# 324_Electrode_Wafer_Schematic.net
KiCad netlist of a schematic drawn in Altium Designer
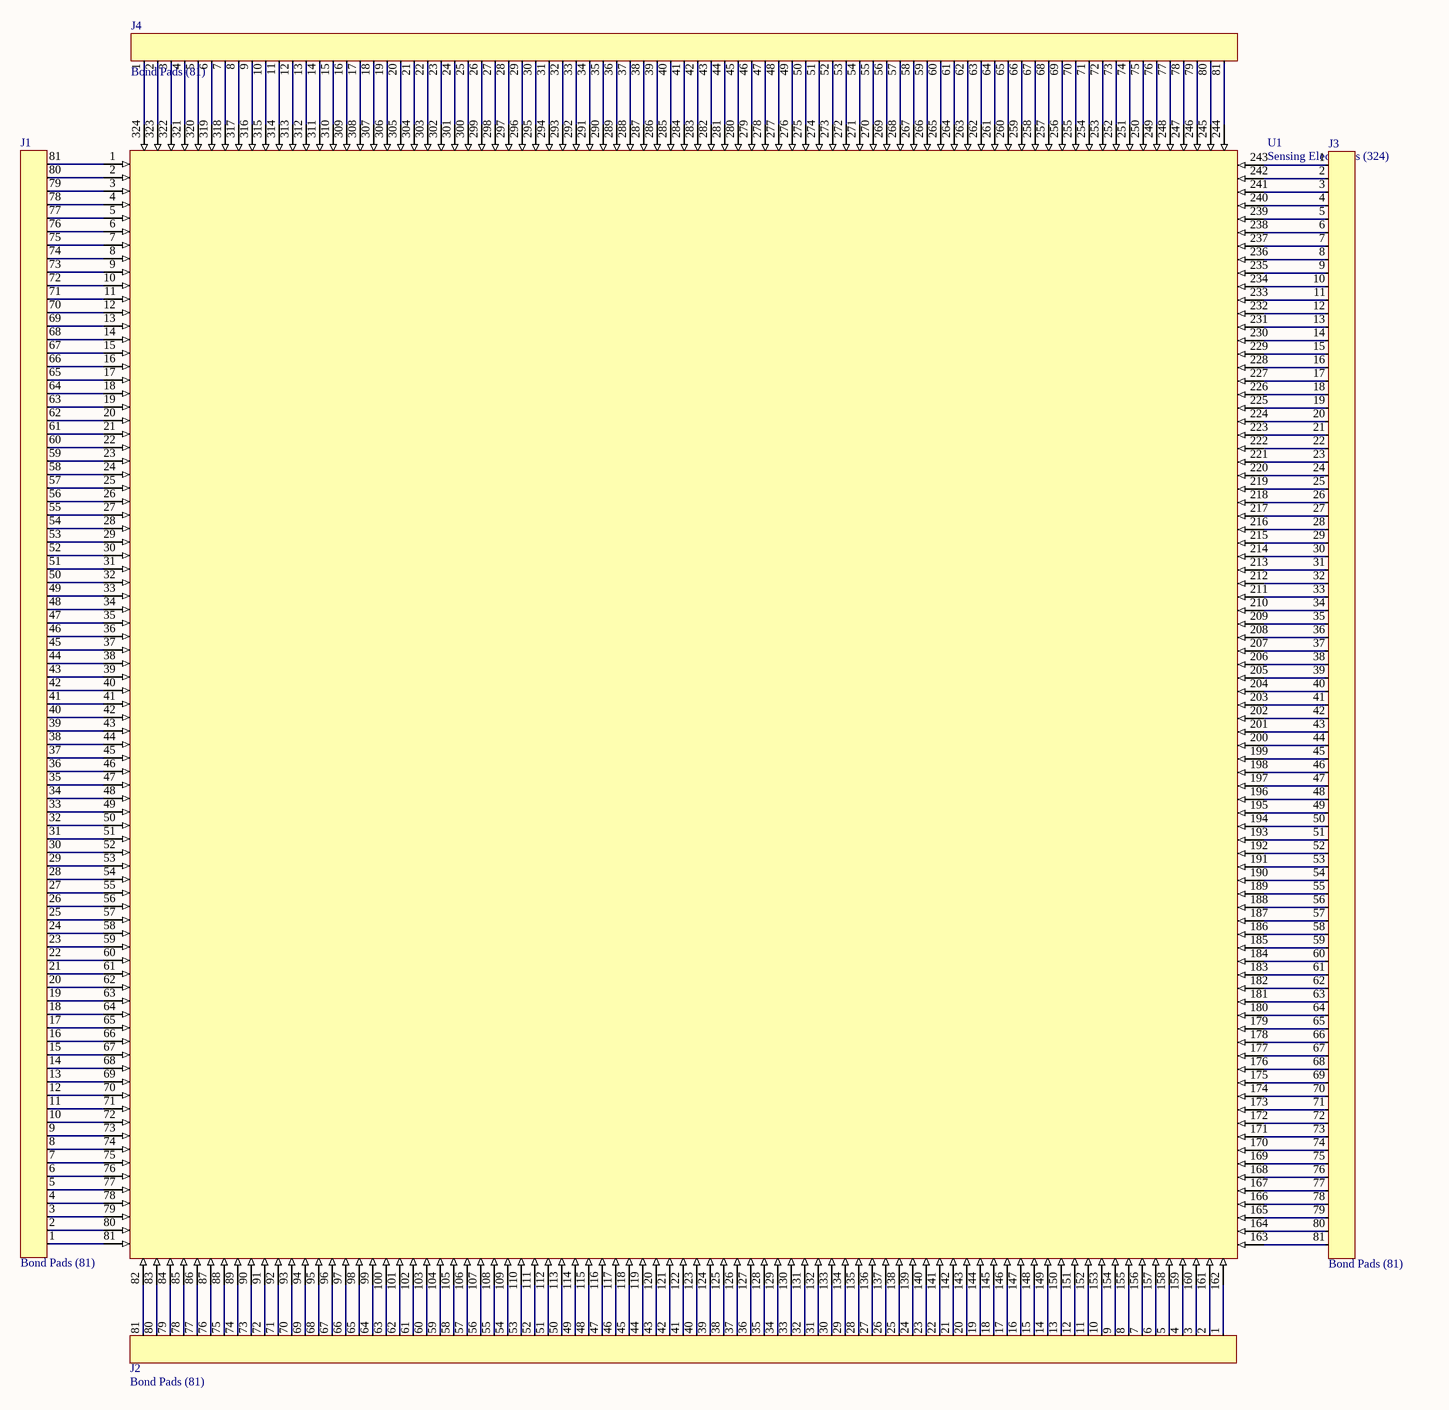
[diagram p0: 324 Electrode Wafer Schematic.SchDoc]

(export (version "E")
  (design (tool "Eeschema 10.0.6"))
  (components
    (comp (ref "J1")
      (value "Bond Pads (81)")
      (footprint "Bond Pads (81)")
      (description "81 pads for all four sides of the chip")
      (libsource (lib "") (part "Bond Pads (81)_1"))
    )
    (comp (ref "J2")
      (value "Bond Pads (81)")
      (footprint "Bond Pads (81)")
      (description "81 pads for all four sides of the chip")
      (libsource (lib "") (part "Bond Pads (81)_3"))
    )
    (comp (ref "J3")
      (value "Bond Pads (81)")
      (footprint "Bond Pads (81)")
      (description "81 pads for all four sides of the chip")
      (libsource (lib "Celestial Library Database") (part "Bond Pads (81)"))
    )
    (comp (ref "J4")
      (value "Bond Pads (81)")
      (footprint "Bond Pads (81)")
      (description "81 pads for all four sides of the chip")
      (libsource (lib "") (part "Bond Pads (81)_2"))
    )
    (comp (ref "U1")
      (value "Sensing Electrodes (324)")
      (footprint "Sensing Area (324)")
      (description "324 Electrodes covering a 2mm by 2mm sensing 10x")
      (fields (field (name "PART NUMBER") "Silicon Die Holder 324 Electrodes"))
      (libsource (lib "Celestial Library Database") (part "Sensing Electrodes (324)"))
    )
  )
  (nets
    (net (code "1") (name "Net-(J1-Pad1)") (class "Default")
      (node (ref "J1") (pin "1") (pintype "input"))
      (node (ref "U1") (pin "81") (pintype "input"))
    )
    (net (code "2") (name "Net-(J1-Pad2)") (class "Default")
      (node (ref "J1") (pin "2") (pintype "input"))
      (node (ref "U1") (pin "80") (pintype "input"))
    )
    (net (code "3") (name "Net-(J1-Pad3)") (class "Default")
      (node (ref "J1") (pin "3") (pintype "input"))
      (node (ref "U1") (pin "79") (pintype "input"))
    )
    (net (code "4") (name "Net-(J1-Pad4)") (class "Default")
      (node (ref "J1") (pin "4") (pintype "input"))
      (node (ref "U1") (pin "78") (pintype "input"))
    )
    (net (code "5") (name "Net-(J1-Pad5)") (class "Default")
      (node (ref "J1") (pin "5") (pintype "input"))
      (node (ref "U1") (pin "77") (pintype "input"))
    )
    (net (code "6") (name "Net-(J1-Pad6)") (class "Default")
      (node (ref "J1") (pin "6") (pintype "input"))
      (node (ref "U1") (pin "76") (pintype "input"))
    )
    (net (code "7") (name "Net-(J1-Pad7)") (class "Default")
      (node (ref "J1") (pin "7") (pintype "input"))
      (node (ref "U1") (pin "75") (pintype "input"))
    )
    (net (code "8") (name "Net-(J1-Pad8)") (class "Default")
      (node (ref "J1") (pin "8") (pintype "input"))
      (node (ref "U1") (pin "74") (pintype "input"))
    )
    (net (code "9") (name "Net-(J1-Pad9)") (class "Default")
      (node (ref "J1") (pin "9") (pintype "input"))
      (node (ref "U1") (pin "73") (pintype "input"))
    )
    (net (code "10") (name "Net-(J1-Pad10)") (class "Default")
      (node (ref "J1") (pin "10") (pintype "input"))
      (node (ref "U1") (pin "72") (pintype "input"))
    )
    (net (code "11") (name "Net-(J1-Pad11)") (class "Default")
      (node (ref "J1") (pin "11") (pintype "input"))
      (node (ref "U1") (pin "71") (pintype "input"))
    )
    (net (code "12") (name "Net-(J1-Pad12)") (class "Default")
      (node (ref "J1") (pin "12") (pintype "input"))
      (node (ref "U1") (pin "70") (pintype "input"))
    )
    (net (code "13") (name "Net-(J1-Pad13)") (class "Default")
      (node (ref "J1") (pin "13") (pintype "input"))
      (node (ref "U1") (pin "69") (pintype "input"))
    )
    (net (code "14") (name "Net-(J1-Pad14)") (class "Default")
      (node (ref "J1") (pin "14") (pintype "input"))
      (node (ref "U1") (pin "68") (pintype "input"))
    )
    (net (code "15") (name "Net-(J1-Pad15)") (class "Default")
      (node (ref "J1") (pin "15") (pintype "input"))
      (node (ref "U1") (pin "67") (pintype "input"))
    )
    (net (code "16") (name "Net-(J1-Pad16)") (class "Default")
      (node (ref "J1") (pin "16") (pintype "input"))
      (node (ref "U1") (pin "66") (pintype "input"))
    )
    (net (code "17") (name "Net-(J1-Pad17)") (class "Default")
      (node (ref "J1") (pin "17") (pintype "input"))
      (node (ref "U1") (pin "65") (pintype "input"))
    )
    (net (code "18") (name "Net-(J1-Pad18)") (class "Default")
      (node (ref "J1") (pin "18") (pintype "input"))
      (node (ref "U1") (pin "64") (pintype "input"))
    )
    (net (code "19") (name "Net-(J1-Pad19)") (class "Default")
      (node (ref "J1") (pin "19") (pintype "input"))
      (node (ref "U1") (pin "63") (pintype "input"))
    )
    (net (code "20") (name "Net-(J1-Pad20)") (class "Default")
      (node (ref "J1") (pin "20") (pintype "input"))
      (node (ref "U1") (pin "62") (pintype "input"))
    )
    (net (code "21") (name "Net-(J1-Pad21)") (class "Default")
      (node (ref "J1") (pin "21") (pintype "input"))
      (node (ref "U1") (pin "61") (pintype "input"))
    )
    (net (code "22") (name "Net-(J1-Pad22)") (class "Default")
      (node (ref "J1") (pin "22") (pintype "input"))
      (node (ref "U1") (pin "60") (pintype "input"))
    )
    (net (code "23") (name "Net-(J1-Pad23)") (class "Default")
      (node (ref "J1") (pin "23") (pintype "input"))
      (node (ref "U1") (pin "59") (pintype "input"))
    )
    (net (code "24") (name "Net-(J1-Pad24)") (class "Default")
      (node (ref "J1") (pin "24") (pintype "input"))
      (node (ref "U1") (pin "58") (pintype "input"))
    )
    (net (code "25") (name "Net-(J1-Pad25)") (class "Default")
      (node (ref "J1") (pin "25") (pintype "input"))
      (node (ref "U1") (pin "57") (pintype "input"))
    )
    (net (code "26") (name "Net-(J1-Pad26)") (class "Default")
      (node (ref "J1") (pin "26") (pintype "input"))
      (node (ref "U1") (pin "56") (pintype "input"))
    )
    (net (code "27") (name "Net-(J1-Pad27)") (class "Default")
      (node (ref "J1") (pin "27") (pintype "input"))
      (node (ref "U1") (pin "55") (pintype "input"))
    )
    (net (code "28") (name "Net-(J1-Pad28)") (class "Default")
      (node (ref "J1") (pin "28") (pintype "input"))
      (node (ref "U1") (pin "54") (pintype "input"))
    )
    (net (code "29") (name "Net-(J1-Pad29)") (class "Default")
      (node (ref "J1") (pin "29") (pintype "input"))
      (node (ref "U1") (pin "53") (pintype "input"))
    )
    (net (code "30") (name "Net-(J1-Pad30)") (class "Default")
      (node (ref "J1") (pin "30") (pintype "input"))
      (node (ref "U1") (pin "52") (pintype "input"))
    )
    (net (code "31") (name "Net-(J1-Pad31)") (class "Default")
      (node (ref "J1") (pin "31") (pintype "input"))
      (node (ref "U1") (pin "51") (pintype "input"))
    )
    (net (code "32") (name "Net-(J1-Pad32)") (class "Default")
      (node (ref "J1") (pin "32") (pintype "input"))
      (node (ref "U1") (pin "50") (pintype "input"))
    )
    (net (code "33") (name "Net-(J1-Pad33)") (class "Default")
      (node (ref "J1") (pin "33") (pintype "input"))
      (node (ref "U1") (pin "49") (pintype "input"))
    )
    (net (code "34") (name "Net-(J1-Pad34)") (class "Default")
      (node (ref "J1") (pin "34") (pintype "input"))
      (node (ref "U1") (pin "48") (pintype "input"))
    )
    (net (code "35") (name "Net-(J1-Pad35)") (class "Default")
      (node (ref "J1") (pin "35") (pintype "input"))
      (node (ref "U1") (pin "47") (pintype "input"))
    )
    (net (code "36") (name "Net-(J1-Pad36)") (class "Default")
      (node (ref "J1") (pin "36") (pintype "input"))
      (node (ref "U1") (pin "46") (pintype "input"))
    )
    (net (code "37") (name "Net-(J1-Pad37)") (class "Default")
      (node (ref "J1") (pin "37") (pintype "input"))
      (node (ref "U1") (pin "45") (pintype "input"))
    )
    (net (code "38") (name "Net-(J1-Pad38)") (class "Default")
      (node (ref "J1") (pin "38") (pintype "input"))
      (node (ref "U1") (pin "44") (pintype "input"))
    )
    (net (code "39") (name "Net-(J1-Pad39)") (class "Default")
      (node (ref "J1") (pin "39") (pintype "input"))
      (node (ref "U1") (pin "43") (pintype "input"))
    )
    (net (code "40") (name "Net-(J1-Pad40)") (class "Default")
      (node (ref "J1") (pin "40") (pintype "input"))
      (node (ref "U1") (pin "42") (pintype "input"))
    )
    (net (code "41") (name "Net-(J1-Pad41)") (class "Default")
      (node (ref "J1") (pin "41") (pintype "input"))
      (node (ref "U1") (pin "41") (pintype "input"))
    )
    (net (code "42") (name "Net-(J1-Pad42)") (class "Default")
      (node (ref "J1") (pin "42") (pintype "input"))
      (node (ref "U1") (pin "40") (pintype "input"))
    )
    (net (code "43") (name "Net-(J1-Pad43)") (class "Default")
      (node (ref "J1") (pin "43") (pintype "input"))
      (node (ref "U1") (pin "39") (pintype "input"))
    )
    (net (code "44") (name "Net-(J1-Pad44)") (class "Default")
      (node (ref "J1") (pin "44") (pintype "input"))
      (node (ref "U1") (pin "38") (pintype "input"))
    )
    (net (code "45") (name "Net-(J1-Pad45)") (class "Default")
      (node (ref "J1") (pin "45") (pintype "input"))
      (node (ref "U1") (pin "37") (pintype "input"))
    )
    (net (code "46") (name "Net-(J1-Pad46)") (class "Default")
      (node (ref "J1") (pin "46") (pintype "input"))
      (node (ref "U1") (pin "36") (pintype "input"))
    )
    (net (code "47") (name "Net-(J1-Pad47)") (class "Default")
      (node (ref "J1") (pin "47") (pintype "input"))
      (node (ref "U1") (pin "35") (pintype "input"))
    )
    (net (code "48") (name "Net-(J1-Pad48)") (class "Default")
      (node (ref "J1") (pin "48") (pintype "input"))
      (node (ref "U1") (pin "34") (pintype "input"))
    )
    (net (code "49") (name "Net-(J1-Pad49)") (class "Default")
      (node (ref "J1") (pin "49") (pintype "input"))
      (node (ref "U1") (pin "33") (pintype "input"))
    )
    (net (code "50") (name "Net-(J1-Pad50)") (class "Default")
      (node (ref "J1") (pin "50") (pintype "input"))
      (node (ref "U1") (pin "32") (pintype "input"))
    )
    (net (code "51") (name "Net-(J1-Pad51)") (class "Default")
      (node (ref "J1") (pin "51") (pintype "input"))
      (node (ref "U1") (pin "31") (pintype "input"))
    )
    (net (code "52") (name "Net-(J1-Pad52)") (class "Default")
      (node (ref "J1") (pin "52") (pintype "input"))
      (node (ref "U1") (pin "30") (pintype "input"))
    )
    (net (code "53") (name "Net-(J1-Pad53)") (class "Default")
      (node (ref "J1") (pin "53") (pintype "input"))
      (node (ref "U1") (pin "29") (pintype "input"))
    )
    (net (code "54") (name "Net-(J1-Pad54)") (class "Default")
      (node (ref "J1") (pin "54") (pintype "input"))
      (node (ref "U1") (pin "28") (pintype "input"))
    )
    (net (code "55") (name "Net-(J1-Pad55)") (class "Default")
      (node (ref "J1") (pin "55") (pintype "input"))
      (node (ref "U1") (pin "27") (pintype "input"))
    )
    (net (code "56") (name "Net-(J1-Pad56)") (class "Default")
      (node (ref "J1") (pin "56") (pintype "input"))
      (node (ref "U1") (pin "26") (pintype "input"))
    )
    (net (code "57") (name "Net-(J1-Pad57)") (class "Default")
      (node (ref "J1") (pin "57") (pintype "input"))
      (node (ref "U1") (pin "25") (pintype "input"))
    )
    (net (code "58") (name "Net-(J1-Pad58)") (class "Default")
      (node (ref "J1") (pin "58") (pintype "input"))
      (node (ref "U1") (pin "24") (pintype "input"))
    )
    (net (code "59") (name "Net-(J1-Pad59)") (class "Default")
      (node (ref "J1") (pin "59") (pintype "input"))
      (node (ref "U1") (pin "23") (pintype "input"))
    )
    (net (code "60") (name "Net-(J1-Pad60)") (class "Default")
      (node (ref "J1") (pin "60") (pintype "input"))
      (node (ref "U1") (pin "22") (pintype "input"))
    )
    (net (code "61") (name "Net-(J1-Pad61)") (class "Default")
      (node (ref "J1") (pin "61") (pintype "input"))
      (node (ref "U1") (pin "21") (pintype "input"))
    )
    (net (code "62") (name "Net-(J1-Pad62)") (class "Default")
      (node (ref "J1") (pin "62") (pintype "input"))
      (node (ref "U1") (pin "20") (pintype "input"))
    )
    (net (code "63") (name "Net-(J1-Pad63)") (class "Default")
      (node (ref "J1") (pin "63") (pintype "input"))
      (node (ref "U1") (pin "19") (pintype "input"))
    )
    (net (code "64") (name "Net-(J1-Pad64)") (class "Default")
      (node (ref "J1") (pin "64") (pintype "input"))
      (node (ref "U1") (pin "18") (pintype "input"))
    )
    (net (code "65") (name "Net-(J1-Pad65)") (class "Default")
      (node (ref "J1") (pin "65") (pintype "input"))
      (node (ref "U1") (pin "17") (pintype "input"))
    )
    (net (code "66") (name "Net-(J1-Pad66)") (class "Default")
      (node (ref "J1") (pin "66") (pintype "input"))
      (node (ref "U1") (pin "16") (pintype "input"))
    )
    (net (code "67") (name "Net-(J1-Pad67)") (class "Default")
      (node (ref "J1") (pin "67") (pintype "input"))
      (node (ref "U1") (pin "15") (pintype "input"))
    )
    (net (code "68") (name "Net-(J1-Pad68)") (class "Default")
      (node (ref "J1") (pin "68") (pintype "input"))
      (node (ref "U1") (pin "14") (pintype "input"))
    )
    (net (code "69") (name "Net-(J1-Pad69)") (class "Default")
      (node (ref "J1") (pin "69") (pintype "input"))
      (node (ref "U1") (pin "13") (pintype "input"))
    )
    (net (code "70") (name "Net-(J1-Pad70)") (class "Default")
      (node (ref "J1") (pin "70") (pintype "input"))
      (node (ref "U1") (pin "12") (pintype "input"))
    )
    (net (code "71") (name "Net-(J1-Pad71)") (class "Default")
      (node (ref "J1") (pin "71") (pintype "input"))
      (node (ref "U1") (pin "11") (pintype "input"))
    )
    (net (code "72") (name "Net-(J1-Pad72)") (class "Default")
      (node (ref "J1") (pin "72") (pintype "input"))
      (node (ref "U1") (pin "10") (pintype "input"))
    )
    (net (code "73") (name "Net-(J1-Pad73)") (class "Default")
      (node (ref "J1") (pin "73") (pintype "input"))
      (node (ref "U1") (pin "9") (pintype "input"))
    )
    (net (code "74") (name "Net-(J1-Pad74)") (class "Default")
      (node (ref "J1") (pin "74") (pintype "input"))
      (node (ref "U1") (pin "8") (pintype "input"))
    )
    (net (code "75") (name "Net-(J1-Pad75)") (class "Default")
      (node (ref "J1") (pin "75") (pintype "input"))
      (node (ref "U1") (pin "7") (pintype "input"))
    )
    (net (code "76") (name "Net-(J1-Pad76)") (class "Default")
      (node (ref "J1") (pin "76") (pintype "input"))
      (node (ref "U1") (pin "6") (pintype "input"))
    )
    (net (code "77") (name "Net-(J1-Pad77)") (class "Default")
      (node (ref "J1") (pin "77") (pintype "input"))
      (node (ref "U1") (pin "5") (pintype "input"))
    )
    (net (code "78") (name "Net-(J1-Pad78)") (class "Default")
      (node (ref "J1") (pin "78") (pintype "input"))
      (node (ref "U1") (pin "4") (pintype "input"))
    )
    (net (code "79") (name "Net-(J1-Pad79)") (class "Default")
      (node (ref "J1") (pin "79") (pintype "input"))
      (node (ref "U1") (pin "3") (pintype "input"))
    )
    (net (code "80") (name "Net-(J1-Pad80)") (class "Default")
      (node (ref "J1") (pin "80") (pintype "input"))
      (node (ref "U1") (pin "2") (pintype "input"))
    )
    (net (code "81") (name "Net-(J1-Pad81)") (class "Default")
      (node (ref "J1") (pin "81") (pintype "input"))
      (node (ref "U1") (pin "1") (pintype "input"))
    )
    (net (code "82") (name "Net-(J2-Pad1)") (class "Default")
      (node (ref "J2") (pin "1") (pintype "input"))
      (node (ref "U1") (pin "162") (pintype "input"))
    )
    (net (code "83") (name "Net-(J2-Pad2)") (class "Default")
      (node (ref "J2") (pin "2") (pintype "input"))
      (node (ref "U1") (pin "161") (pintype "input"))
    )
    (net (code "84") (name "Net-(J2-Pad3)") (class "Default")
      (node (ref "J2") (pin "3") (pintype "input"))
      (node (ref "U1") (pin "160") (pintype "input"))
    )
    (net (code "85") (name "Net-(J2-Pad4)") (class "Default")
      (node (ref "J2") (pin "4") (pintype "input"))
      (node (ref "U1") (pin "159") (pintype "input"))
    )
    (net (code "86") (name "Net-(J2-Pad5)") (class "Default")
      (node (ref "J2") (pin "5") (pintype "input"))
      (node (ref "U1") (pin "158") (pintype "input"))
    )
    (net (code "87") (name "Net-(J2-Pad6)") (class "Default")
      (node (ref "J2") (pin "6") (pintype "input"))
      (node (ref "U1") (pin "157") (pintype "input"))
    )
    (net (code "88") (name "Net-(J2-Pad7)") (class "Default")
      (node (ref "J2") (pin "7") (pintype "input"))
      (node (ref "U1") (pin "156") (pintype "input"))
    )
    (net (code "89") (name "Net-(J2-Pad8)") (class "Default")
      (node (ref "J2") (pin "8") (pintype "input"))
      (node (ref "U1") (pin "155") (pintype "input"))
    )
    (net (code "90") (name "Net-(J2-Pad9)") (class "Default")
      (node (ref "J2") (pin "9") (pintype "input"))
      (node (ref "U1") (pin "154") (pintype "input"))
    )
    (net (code "91") (name "Net-(J2-Pad10)") (class "Default")
      (node (ref "J2") (pin "10") (pintype "input"))
      (node (ref "U1") (pin "153") (pintype "input"))
    )
    (net (code "92") (name "Net-(J2-Pad11)") (class "Default")
      (node (ref "J2") (pin "11") (pintype "input"))
      (node (ref "U1") (pin "152") (pintype "input"))
    )
    (net (code "93") (name "Net-(J2-Pad12)") (class "Default")
      (node (ref "J2") (pin "12") (pintype "input"))
      (node (ref "U1") (pin "151") (pintype "input"))
    )
    (net (code "94") (name "Net-(J2-Pad13)") (class "Default")
      (node (ref "J2") (pin "13") (pintype "input"))
      (node (ref "U1") (pin "150") (pintype "input"))
    )
    (net (code "95") (name "Net-(J2-Pad14)") (class "Default")
      (node (ref "J2") (pin "14") (pintype "input"))
      (node (ref "U1") (pin "149") (pintype "input"))
    )
    (net (code "96") (name "Net-(J2-Pad15)") (class "Default")
      (node (ref "J2") (pin "15") (pintype "input"))
      (node (ref "U1") (pin "148") (pintype "input"))
    )
    (net (code "97") (name "Net-(J2-Pad16)") (class "Default")
      (node (ref "J2") (pin "16") (pintype "input"))
      (node (ref "U1") (pin "147") (pintype "input"))
    )
    (net (code "98") (name "Net-(J2-Pad17)") (class "Default")
      (node (ref "J2") (pin "17") (pintype "input"))
      (node (ref "U1") (pin "146") (pintype "input"))
    )
    (net (code "99") (name "Net-(J2-Pad18)") (class "Default")
      (node (ref "J2") (pin "18") (pintype "input"))
      (node (ref "U1") (pin "145") (pintype "input"))
    )
    (net (code "100") (name "Net-(J2-Pad19)") (class "Default")
      (node (ref "J2") (pin "19") (pintype "input"))
      (node (ref "U1") (pin "144") (pintype "input"))
    )
    (net (code "101") (name "Net-(J2-Pad20)") (class "Default")
      (node (ref "J2") (pin "20") (pintype "input"))
      (node (ref "U1") (pin "143") (pintype "input"))
    )
    (net (code "102") (name "Net-(J2-Pad21)") (class "Default")
      (node (ref "J2") (pin "21") (pintype "input"))
      (node (ref "U1") (pin "142") (pintype "input"))
    )
    (net (code "103") (name "Net-(J2-Pad22)") (class "Default")
      (node (ref "J2") (pin "22") (pintype "input"))
      (node (ref "U1") (pin "141") (pintype "input"))
    )
    (net (code "104") (name "Net-(J2-Pad23)") (class "Default")
      (node (ref "J2") (pin "23") (pintype "input"))
      (node (ref "U1") (pin "140") (pintype "input"))
    )
    (net (code "105") (name "Net-(J2-Pad24)") (class "Default")
      (node (ref "J2") (pin "24") (pintype "input"))
      (node (ref "U1") (pin "139") (pintype "input"))
    )
    (net (code "106") (name "Net-(J2-Pad25)") (class "Default")
      (node (ref "J2") (pin "25") (pintype "input"))
      (node (ref "U1") (pin "138") (pintype "input"))
    )
    (net (code "107") (name "Net-(J2-Pad26)") (class "Default")
      (node (ref "J2") (pin "26") (pintype "input"))
      (node (ref "U1") (pin "137") (pintype "input"))
    )
    (net (code "108") (name "Net-(J2-Pad27)") (class "Default")
      (node (ref "J2") (pin "27") (pintype "input"))
      (node (ref "U1") (pin "136") (pintype "input"))
    )
    (net (code "109") (name "Net-(J2-Pad28)") (class "Default")
      (node (ref "J2") (pin "28") (pintype "input"))
      (node (ref "U1") (pin "135") (pintype "input"))
    )
    (net (code "110") (name "Net-(J2-Pad29)") (class "Default")
      (node (ref "J2") (pin "29") (pintype "input"))
      (node (ref "U1") (pin "134") (pintype "input"))
    )
    (net (code "111") (name "Net-(J2-Pad30)") (class "Default")
      (node (ref "J2") (pin "30") (pintype "input"))
      (node (ref "U1") (pin "133") (pintype "input"))
    )
    (net (code "112") (name "Net-(J2-Pad31)") (class "Default")
      (node (ref "J2") (pin "31") (pintype "input"))
      (node (ref "U1") (pin "132") (pintype "input"))
    )
    (net (code "113") (name "Net-(J2-Pad32)") (class "Default")
      (node (ref "J2") (pin "32") (pintype "input"))
      (node (ref "U1") (pin "131") (pintype "input"))
    )
    (net (code "114") (name "Net-(J2-Pad33)") (class "Default")
      (node (ref "J2") (pin "33") (pintype "input"))
      (node (ref "U1") (pin "130") (pintype "input"))
    )
    (net (code "115") (name "Net-(J2-Pad34)") (class "Default")
      (node (ref "J2") (pin "34") (pintype "input"))
      (node (ref "U1") (pin "129") (pintype "input"))
    )
    (net (code "116") (name "Net-(J2-Pad35)") (class "Default")
      (node (ref "J2") (pin "35") (pintype "input"))
      (node (ref "U1") (pin "128") (pintype "input"))
    )
    (net (code "117") (name "Net-(J2-Pad36)") (class "Default")
      (node (ref "J2") (pin "36") (pintype "input"))
      (node (ref "U1") (pin "127") (pintype "input"))
    )
    (net (code "118") (name "Net-(J2-Pad37)") (class "Default")
      (node (ref "J2") (pin "37") (pintype "input"))
      (node (ref "U1") (pin "126") (pintype "input"))
    )
    (net (code "119") (name "Net-(J2-Pad38)") (class "Default")
      (node (ref "J2") (pin "38") (pintype "input"))
      (node (ref "U1") (pin "125") (pintype "input"))
    )
    (net (code "120") (name "Net-(J2-Pad39)") (class "Default")
      (node (ref "J2") (pin "39") (pintype "input"))
      (node (ref "U1") (pin "124") (pintype "input"))
    )
    (net (code "121") (name "Net-(J2-Pad40)") (class "Default")
      (node (ref "J2") (pin "40") (pintype "input"))
      (node (ref "U1") (pin "123") (pintype "input"))
    )
    (net (code "122") (name "Net-(J2-Pad41)") (class "Default")
      (node (ref "J2") (pin "41") (pintype "input"))
      (node (ref "U1") (pin "122") (pintype "input"))
    )
    (net (code "123") (name "Net-(J2-Pad42)") (class "Default")
      (node (ref "J2") (pin "42") (pintype "input"))
      (node (ref "U1") (pin "121") (pintype "input"))
    )
    (net (code "124") (name "Net-(J2-Pad43)") (class "Default")
      (node (ref "J2") (pin "43") (pintype "input"))
      (node (ref "U1") (pin "120") (pintype "input"))
    )
    (net (code "125") (name "Net-(J2-Pad44)") (class "Default")
      (node (ref "J2") (pin "44") (pintype "input"))
      (node (ref "U1") (pin "119") (pintype "input"))
    )
    (net (code "126") (name "Net-(J2-Pad45)") (class "Default")
      (node (ref "J2") (pin "45") (pintype "input"))
      (node (ref "U1") (pin "118") (pintype "input"))
    )
    (net (code "127") (name "Net-(J2-Pad46)") (class "Default")
      (node (ref "J2") (pin "46") (pintype "input"))
      (node (ref "U1") (pin "117") (pintype "input"))
    )
    (net (code "128") (name "Net-(J2-Pad47)") (class "Default")
      (node (ref "J2") (pin "47") (pintype "input"))
      (node (ref "U1") (pin "116") (pintype "input"))
    )
    (net (code "129") (name "Net-(J2-Pad48)") (class "Default")
      (node (ref "J2") (pin "48") (pintype "input"))
      (node (ref "U1") (pin "115") (pintype "input"))
    )
    (net (code "130") (name "Net-(J2-Pad49)") (class "Default")
      (node (ref "J2") (pin "49") (pintype "input"))
      (node (ref "U1") (pin "114") (pintype "input"))
    )
    (net (code "131") (name "Net-(J2-Pad50)") (class "Default")
      (node (ref "J2") (pin "50") (pintype "input"))
      (node (ref "U1") (pin "113") (pintype "input"))
    )
    (net (code "132") (name "Net-(J2-Pad51)") (class "Default")
      (node (ref "J2") (pin "51") (pintype "input"))
      (node (ref "U1") (pin "112") (pintype "input"))
    )
    (net (code "133") (name "Net-(J2-Pad52)") (class "Default")
      (node (ref "J2") (pin "52") (pintype "input"))
      (node (ref "U1") (pin "111") (pintype "input"))
    )
    (net (code "134") (name "Net-(J2-Pad53)") (class "Default")
      (node (ref "J2") (pin "53") (pintype "input"))
      (node (ref "U1") (pin "110") (pintype "input"))
    )
    (net (code "135") (name "Net-(J2-Pad54)") (class "Default")
      (node (ref "J2") (pin "54") (pintype "input"))
      (node (ref "U1") (pin "109") (pintype "input"))
    )
    (net (code "136") (name "Net-(J2-Pad55)") (class "Default")
      (node (ref "J2") (pin "55") (pintype "input"))
      (node (ref "U1") (pin "108") (pintype "input"))
    )
    (net (code "137") (name "Net-(J2-Pad56)") (class "Default")
      (node (ref "J2") (pin "56") (pintype "input"))
      (node (ref "U1") (pin "107") (pintype "input"))
    )
    (net (code "138") (name "Net-(J2-Pad57)") (class "Default")
      (node (ref "J2") (pin "57") (pintype "input"))
      (node (ref "U1") (pin "106") (pintype "input"))
    )
    (net (code "139") (name "Net-(J2-Pad58)") (class "Default")
      (node (ref "J2") (pin "58") (pintype "input"))
      (node (ref "U1") (pin "105") (pintype "input"))
    )
    (net (code "140") (name "Net-(J2-Pad59)") (class "Default")
      (node (ref "J2") (pin "59") (pintype "input"))
      (node (ref "U1") (pin "104") (pintype "input"))
    )
    (net (code "141") (name "Net-(J2-Pad60)") (class "Default")
      (node (ref "J2") (pin "60") (pintype "input"))
      (node (ref "U1") (pin "103") (pintype "input"))
    )
    (net (code "142") (name "Net-(J2-Pad61)") (class "Default")
      (node (ref "J2") (pin "61") (pintype "input"))
      (node (ref "U1") (pin "102") (pintype "input"))
    )
    (net (code "143") (name "Net-(J2-Pad62)") (class "Default")
      (node (ref "J2") (pin "62") (pintype "input"))
      (node (ref "U1") (pin "101") (pintype "input"))
    )
    (net (code "144") (name "Net-(J2-Pad63)") (class "Default")
      (node (ref "J2") (pin "63") (pintype "input"))
      (node (ref "U1") (pin "100") (pintype "input"))
    )
    (net (code "145") (name "Net-(J2-Pad64)") (class "Default")
      (node (ref "J2") (pin "64") (pintype "input"))
      (node (ref "U1") (pin "99") (pintype "input"))
    )
    (net (code "146") (name "Net-(J2-Pad65)") (class "Default")
      (node (ref "J2") (pin "65") (pintype "input"))
      (node (ref "U1") (pin "98") (pintype "input"))
    )
    (net (code "147") (name "Net-(J2-Pad66)") (class "Default")
      (node (ref "J2") (pin "66") (pintype "input"))
      (node (ref "U1") (pin "97") (pintype "input"))
    )
    (net (code "148") (name "Net-(J2-Pad67)") (class "Default")
      (node (ref "J2") (pin "67") (pintype "input"))
      (node (ref "U1") (pin "96") (pintype "input"))
    )
    (net (code "149") (name "Net-(J2-Pad68)") (class "Default")
      (node (ref "J2") (pin "68") (pintype "input"))
      (node (ref "U1") (pin "95") (pintype "input"))
    )
    (net (code "150") (name "Net-(J2-Pad69)") (class "Default")
      (node (ref "J2") (pin "69") (pintype "input"))
      (node (ref "U1") (pin "94") (pintype "input"))
    )
    (net (code "151") (name "Net-(J2-Pad70)") (class "Default")
      (node (ref "J2") (pin "70") (pintype "input"))
      (node (ref "U1") (pin "93") (pintype "input"))
    )
    (net (code "152") (name "Net-(J2-Pad71)") (class "Default")
      (node (ref "J2") (pin "71") (pintype "input"))
      (node (ref "U1") (pin "92") (pintype "input"))
    )
    (net (code "153") (name "Net-(J2-Pad72)") (class "Default")
      (node (ref "J2") (pin "72") (pintype "input"))
      (node (ref "U1") (pin "91") (pintype "input"))
    )
    (net (code "154") (name "Net-(J2-Pad73)") (class "Default")
      (node (ref "J2") (pin "73") (pintype "input"))
      (node (ref "U1") (pin "90") (pintype "input"))
    )
    (net (code "155") (name "Net-(J2-Pad74)") (class "Default")
      (node (ref "J2") (pin "74") (pintype "input"))
      (node (ref "U1") (pin "89") (pintype "input"))
    )
    (net (code "156") (name "Net-(J2-Pad75)") (class "Default")
      (node (ref "J2") (pin "75") (pintype "input"))
      (node (ref "U1") (pin "88") (pintype "input"))
    )
    (net (code "157") (name "Net-(J2-Pad76)") (class "Default")
      (node (ref "J2") (pin "76") (pintype "input"))
      (node (ref "U1") (pin "87") (pintype "input"))
    )
    (net (code "158") (name "Net-(J2-Pad77)") (class "Default")
      (node (ref "J2") (pin "77") (pintype "input"))
      (node (ref "U1") (pin "86") (pintype "input"))
    )
    (net (code "159") (name "Net-(J2-Pad78)") (class "Default")
      (node (ref "J2") (pin "78") (pintype "input"))
      (node (ref "U1") (pin "85") (pintype "input"))
    )
    (net (code "160") (name "Net-(J2-Pad79)") (class "Default")
      (node (ref "J2") (pin "79") (pintype "input"))
      (node (ref "U1") (pin "84") (pintype "input"))
    )
    (net (code "161") (name "Net-(J2-Pad80)") (class "Default")
      (node (ref "J2") (pin "80") (pintype "input"))
      (node (ref "U1") (pin "83") (pintype "input"))
    )
    (net (code "162") (name "Net-(J2-Pad81)") (class "Default")
      (node (ref "J2") (pin "81") (pintype "input"))
      (node (ref "U1") (pin "82") (pintype "input"))
    )
    (net (code "163") (name "Net-(J3-Pad1)") (class "Default")
      (node (ref "J3") (pin "1") (pintype "input"))
      (node (ref "U1") (pin "243") (pintype "input"))
    )
    (net (code "164") (name "Net-(J3-Pad2)") (class "Default")
      (node (ref "J3") (pin "2") (pintype "input"))
      (node (ref "U1") (pin "242") (pintype "input"))
    )
    (net (code "165") (name "Net-(J3-Pad3)") (class "Default")
      (node (ref "J3") (pin "3") (pintype "input"))
      (node (ref "U1") (pin "241") (pintype "input"))
    )
    (net (code "166") (name "Net-(J3-Pad4)") (class "Default")
      (node (ref "J3") (pin "4") (pintype "input"))
      (node (ref "U1") (pin "240") (pintype "input"))
    )
    (net (code "167") (name "Net-(J3-Pad5)") (class "Default")
      (node (ref "J3") (pin "5") (pintype "input"))
      (node (ref "U1") (pin "239") (pintype "input"))
    )
    (net (code "168") (name "Net-(J3-Pad6)") (class "Default")
      (node (ref "J3") (pin "6") (pintype "input"))
      (node (ref "U1") (pin "238") (pintype "input"))
    )
    (net (code "169") (name "Net-(J3-Pad7)") (class "Default")
      (node (ref "J3") (pin "7") (pintype "input"))
      (node (ref "U1") (pin "237") (pintype "input"))
    )
    (net (code "170") (name "Net-(J3-Pad8)") (class "Default")
      (node (ref "J3") (pin "8") (pintype "input"))
      (node (ref "U1") (pin "236") (pintype "input"))
    )
    (net (code "171") (name "Net-(J3-Pad9)") (class "Default")
      (node (ref "J3") (pin "9") (pintype "input"))
      (node (ref "U1") (pin "235") (pintype "input"))
    )
    (net (code "172") (name "Net-(J3-Pad10)") (class "Default")
      (node (ref "J3") (pin "10") (pintype "input"))
      (node (ref "U1") (pin "234") (pintype "input"))
    )
    (net (code "173") (name "Net-(J3-Pad11)") (class "Default")
      (node (ref "J3") (pin "11") (pintype "input"))
      (node (ref "U1") (pin "233") (pintype "input"))
    )
    (net (code "174") (name "Net-(J3-Pad12)") (class "Default")
      (node (ref "J3") (pin "12") (pintype "input"))
      (node (ref "U1") (pin "232") (pintype "input"))
    )
    (net (code "175") (name "Net-(J3-Pad13)") (class "Default")
      (node (ref "J3") (pin "13") (pintype "input"))
      (node (ref "U1") (pin "231") (pintype "input"))
    )
    (net (code "176") (name "Net-(J3-Pad14)") (class "Default")
      (node (ref "J3") (pin "14") (pintype "input"))
      (node (ref "U1") (pin "230") (pintype "input"))
    )
    (net (code "177") (name "Net-(J3-Pad15)") (class "Default")
      (node (ref "J3") (pin "15") (pintype "input"))
      (node (ref "U1") (pin "229") (pintype "input"))
    )
    (net (code "178") (name "Net-(J3-Pad16)") (class "Default")
      (node (ref "J3") (pin "16") (pintype "input"))
      (node (ref "U1") (pin "228") (pintype "input"))
    )
    (net (code "179") (name "Net-(J3-Pad17)") (class "Default")
      (node (ref "J3") (pin "17") (pintype "input"))
      (node (ref "U1") (pin "227") (pintype "input"))
    )
    (net (code "180") (name "Net-(J3-Pad18)") (class "Default")
      (node (ref "J3") (pin "18") (pintype "input"))
      (node (ref "U1") (pin "226") (pintype "input"))
    )
    (net (code "181") (name "Net-(J3-Pad19)") (class "Default")
      (node (ref "J3") (pin "19") (pintype "input"))
      (node (ref "U1") (pin "225") (pintype "input"))
    )
    (net (code "182") (name "Net-(J3-Pad20)") (class "Default")
      (node (ref "J3") (pin "20") (pintype "input"))
      (node (ref "U1") (pin "224") (pintype "input"))
    )
    (net (code "183") (name "Net-(J3-Pad21)") (class "Default")
      (node (ref "J3") (pin "21") (pintype "input"))
      (node (ref "U1") (pin "223") (pintype "input"))
    )
    (net (code "184") (name "Net-(J3-Pad22)") (class "Default")
      (node (ref "J3") (pin "22") (pintype "input"))
      (node (ref "U1") (pin "222") (pintype "input"))
    )
    (net (code "185") (name "Net-(J3-Pad23)") (class "Default")
      (node (ref "J3") (pin "23") (pintype "input"))
      (node (ref "U1") (pin "221") (pintype "input"))
    )
    (net (code "186") (name "Net-(J3-Pad24)") (class "Default")
      (node (ref "J3") (pin "24") (pintype "input"))
      (node (ref "U1") (pin "220") (pintype "input"))
    )
    (net (code "187") (name "Net-(J3-Pad25)") (class "Default")
      (node (ref "J3") (pin "25") (pintype "input"))
      (node (ref "U1") (pin "219") (pintype "input"))
    )
    (net (code "188") (name "Net-(J3-Pad26)") (class "Default")
      (node (ref "J3") (pin "26") (pintype "input"))
      (node (ref "U1") (pin "218") (pintype "input"))
    )
    (net (code "189") (name "Net-(J3-Pad27)") (class "Default")
      (node (ref "J3") (pin "27") (pintype "input"))
      (node (ref "U1") (pin "217") (pintype "input"))
    )
    (net (code "190") (name "Net-(J3-Pad28)") (class "Default")
      (node (ref "J3") (pin "28") (pintype "input"))
      (node (ref "U1") (pin "216") (pintype "input"))
    )
    (net (code "191") (name "Net-(J3-Pad29)") (class "Default")
      (node (ref "J3") (pin "29") (pintype "input"))
      (node (ref "U1") (pin "215") (pintype "input"))
    )
    (net (code "192") (name "Net-(J3-Pad30)") (class "Default")
      (node (ref "J3") (pin "30") (pintype "input"))
      (node (ref "U1") (pin "214") (pintype "input"))
    )
    (net (code "193") (name "Net-(J3-Pad31)") (class "Default")
      (node (ref "J3") (pin "31") (pintype "input"))
      (node (ref "U1") (pin "213") (pintype "input"))
    )
    (net (code "194") (name "Net-(J3-Pad32)") (class "Default")
      (node (ref "J3") (pin "32") (pintype "input"))
      (node (ref "U1") (pin "212") (pintype "input"))
    )
    (net (code "195") (name "Net-(J3-Pad33)") (class "Default")
      (node (ref "J3") (pin "33") (pintype "input"))
      (node (ref "U1") (pin "211") (pintype "input"))
    )
    (net (code "196") (name "Net-(J3-Pad34)") (class "Default")
      (node (ref "J3") (pin "34") (pintype "input"))
      (node (ref "U1") (pin "210") (pintype "input"))
    )
    (net (code "197") (name "Net-(J3-Pad35)") (class "Default")
      (node (ref "J3") (pin "35") (pintype "input"))
      (node (ref "U1") (pin "209") (pintype "input"))
    )
    (net (code "198") (name "Net-(J3-Pad36)") (class "Default")
      (node (ref "J3") (pin "36") (pintype "input"))
      (node (ref "U1") (pin "208") (pintype "input"))
    )
    (net (code "199") (name "Net-(J3-Pad37)") (class "Default")
      (node (ref "J3") (pin "37") (pintype "input"))
      (node (ref "U1") (pin "207") (pintype "input"))
    )
    (net (code "200") (name "Net-(J3-Pad38)") (class "Default")
      (node (ref "J3") (pin "38") (pintype "input"))
      (node (ref "U1") (pin "206") (pintype "input"))
    )
    (net (code "201") (name "Net-(J3-Pad39)") (class "Default")
      (node (ref "J3") (pin "39") (pintype "input"))
      (node (ref "U1") (pin "205") (pintype "input"))
    )
    (net (code "202") (name "Net-(J3-Pad40)") (class "Default")
      (node (ref "J3") (pin "40") (pintype "input"))
      (node (ref "U1") (pin "204") (pintype "input"))
    )
    (net (code "203") (name "Net-(J3-Pad41)") (class "Default")
      (node (ref "J3") (pin "41") (pintype "input"))
      (node (ref "U1") (pin "203") (pintype "input"))
    )
    (net (code "204") (name "Net-(J3-Pad42)") (class "Default")
      (node (ref "J3") (pin "42") (pintype "input"))
      (node (ref "U1") (pin "202") (pintype "input"))
    )
    (net (code "205") (name "Net-(J3-Pad43)") (class "Default")
      (node (ref "J3") (pin "43") (pintype "input"))
      (node (ref "U1") (pin "201") (pintype "input"))
    )
    (net (code "206") (name "Net-(J3-Pad44)") (class "Default")
      (node (ref "J3") (pin "44") (pintype "input"))
      (node (ref "U1") (pin "200") (pintype "input"))
    )
    (net (code "207") (name "Net-(J3-Pad45)") (class "Default")
      (node (ref "J3") (pin "45") (pintype "input"))
      (node (ref "U1") (pin "199") (pintype "input"))
    )
    (net (code "208") (name "Net-(J3-Pad46)") (class "Default")
      (node (ref "J3") (pin "46") (pintype "input"))
      (node (ref "U1") (pin "198") (pintype "input"))
    )
    (net (code "209") (name "Net-(J3-Pad47)") (class "Default")
      (node (ref "J3") (pin "47") (pintype "input"))
      (node (ref "U1") (pin "197") (pintype "input"))
    )
    (net (code "210") (name "Net-(J3-Pad48)") (class "Default")
      (node (ref "J3") (pin "48") (pintype "input"))
      (node (ref "U1") (pin "196") (pintype "input"))
    )
    (net (code "211") (name "Net-(J3-Pad49)") (class "Default")
      (node (ref "J3") (pin "49") (pintype "input"))
      (node (ref "U1") (pin "195") (pintype "input"))
    )
    (net (code "212") (name "Net-(J3-Pad50)") (class "Default")
      (node (ref "J3") (pin "50") (pintype "input"))
      (node (ref "U1") (pin "194") (pintype "input"))
    )
    (net (code "213") (name "Net-(J3-Pad51)") (class "Default")
      (node (ref "J3") (pin "51") (pintype "input"))
      (node (ref "U1") (pin "193") (pintype "input"))
    )
    (net (code "214") (name "Net-(J3-Pad52)") (class "Default")
      (node (ref "J3") (pin "52") (pintype "input"))
      (node (ref "U1") (pin "192") (pintype "input"))
    )
    (net (code "215") (name "Net-(J3-Pad53)") (class "Default")
      (node (ref "J3") (pin "53") (pintype "input"))
      (node (ref "U1") (pin "191") (pintype "input"))
    )
    (net (code "216") (name "Net-(J3-Pad54)") (class "Default")
      (node (ref "J3") (pin "54") (pintype "input"))
      (node (ref "U1") (pin "190") (pintype "input"))
    )
    (net (code "217") (name "Net-(J3-Pad55)") (class "Default")
      (node (ref "J3") (pin "55") (pintype "input"))
      (node (ref "U1") (pin "189") (pintype "input"))
    )
    (net (code "218") (name "Net-(J3-Pad56)") (class "Default")
      (node (ref "J3") (pin "56") (pintype "input"))
      (node (ref "U1") (pin "188") (pintype "input"))
    )
    (net (code "219") (name "Net-(J3-Pad57)") (class "Default")
      (node (ref "J3") (pin "57") (pintype "input"))
      (node (ref "U1") (pin "187") (pintype "input"))
    )
    (net (code "220") (name "Net-(J3-Pad58)") (class "Default")
      (node (ref "J3") (pin "58") (pintype "input"))
      (node (ref "U1") (pin "186") (pintype "input"))
    )
    (net (code "221") (name "Net-(J3-Pad59)") (class "Default")
      (node (ref "J3") (pin "59") (pintype "input"))
      (node (ref "U1") (pin "185") (pintype "input"))
    )
    (net (code "222") (name "Net-(J3-Pad60)") (class "Default")
      (node (ref "J3") (pin "60") (pintype "input"))
      (node (ref "U1") (pin "184") (pintype "input"))
    )
    (net (code "223") (name "Net-(J3-Pad61)") (class "Default")
      (node (ref "J3") (pin "61") (pintype "input"))
      (node (ref "U1") (pin "183") (pintype "input"))
    )
    (net (code "224") (name "Net-(J3-Pad62)") (class "Default")
      (node (ref "J3") (pin "62") (pintype "input"))
      (node (ref "U1") (pin "182") (pintype "input"))
    )
    (net (code "225") (name "Net-(J3-Pad63)") (class "Default")
      (node (ref "J3") (pin "63") (pintype "input"))
      (node (ref "U1") (pin "181") (pintype "input"))
    )
    (net (code "226") (name "Net-(J3-Pad64)") (class "Default")
      (node (ref "J3") (pin "64") (pintype "input"))
      (node (ref "U1") (pin "180") (pintype "input"))
    )
    (net (code "227") (name "Net-(J3-Pad65)") (class "Default")
      (node (ref "J3") (pin "65") (pintype "input"))
      (node (ref "U1") (pin "179") (pintype "input"))
    )
    (net (code "228") (name "Net-(J3-Pad66)") (class "Default")
      (node (ref "J3") (pin "66") (pintype "input"))
      (node (ref "U1") (pin "178") (pintype "input"))
    )
    (net (code "229") (name "Net-(J3-Pad67)") (class "Default")
      (node (ref "J3") (pin "67") (pintype "input"))
      (node (ref "U1") (pin "177") (pintype "input"))
    )
    (net (code "230") (name "Net-(J3-Pad68)") (class "Default")
      (node (ref "J3") (pin "68") (pintype "input"))
      (node (ref "U1") (pin "176") (pintype "input"))
    )
    (net (code "231") (name "Net-(J3-Pad69)") (class "Default")
      (node (ref "J3") (pin "69") (pintype "input"))
      (node (ref "U1") (pin "175") (pintype "input"))
    )
    (net (code "232") (name "Net-(J3-Pad70)") (class "Default")
      (node (ref "J3") (pin "70") (pintype "input"))
      (node (ref "U1") (pin "174") (pintype "input"))
    )
    (net (code "233") (name "Net-(J3-Pad71)") (class "Default")
      (node (ref "J3") (pin "71") (pintype "input"))
      (node (ref "U1") (pin "173") (pintype "input"))
    )
    (net (code "234") (name "Net-(J3-Pad72)") (class "Default")
      (node (ref "J3") (pin "72") (pintype "input"))
      (node (ref "U1") (pin "172") (pintype "input"))
    )
    (net (code "235") (name "Net-(J3-Pad73)") (class "Default")
      (node (ref "J3") (pin "73") (pintype "input"))
      (node (ref "U1") (pin "171") (pintype "input"))
    )
    (net (code "236") (name "Net-(J3-Pad74)") (class "Default")
      (node (ref "J3") (pin "74") (pintype "input"))
      (node (ref "U1") (pin "170") (pintype "input"))
    )
    (net (code "237") (name "Net-(J3-Pad75)") (class "Default")
      (node (ref "J3") (pin "75") (pintype "input"))
      (node (ref "U1") (pin "169") (pintype "input"))
    )
    (net (code "238") (name "Net-(J3-Pad76)") (class "Default")
      (node (ref "J3") (pin "76") (pintype "input"))
      (node (ref "U1") (pin "168") (pintype "input"))
    )
    (net (code "239") (name "Net-(J3-Pad77)") (class "Default")
      (node (ref "J3") (pin "77") (pintype "input"))
      (node (ref "U1") (pin "167") (pintype "input"))
    )
    (net (code "240") (name "Net-(J3-Pad78)") (class "Default")
      (node (ref "J3") (pin "78") (pintype "input"))
      (node (ref "U1") (pin "166") (pintype "input"))
    )
    (net (code "241") (name "Net-(J3-Pad79)") (class "Default")
      (node (ref "J3") (pin "79") (pintype "input"))
      (node (ref "U1") (pin "165") (pintype "input"))
    )
    (net (code "242") (name "Net-(J3-Pad80)") (class "Default")
      (node (ref "J3") (pin "80") (pintype "input"))
      (node (ref "U1") (pin "164") (pintype "input"))
    )
    (net (code "243") (name "Net-(J3-Pad81)") (class "Default")
      (node (ref "J3") (pin "81") (pintype "input"))
      (node (ref "U1") (pin "163") (pintype "input"))
    )
    (net (code "244") (name "Net-(J4-Pad1)") (class "Default")
      (node (ref "J4") (pin "1") (pintype "input"))
      (node (ref "U1") (pin "324") (pintype "input"))
    )
    (net (code "245") (name "Net-(J4-Pad2)") (class "Default")
      (node (ref "J4") (pin "2") (pintype "input"))
      (node (ref "U1") (pin "323") (pintype "input"))
    )
    (net (code "246") (name "Net-(J4-Pad3)") (class "Default")
      (node (ref "J4") (pin "3") (pintype "input"))
      (node (ref "U1") (pin "322") (pintype "input"))
    )
    (net (code "247") (name "Net-(J4-Pad4)") (class "Default")
      (node (ref "J4") (pin "4") (pintype "input"))
      (node (ref "U1") (pin "321") (pintype "input"))
    )
    (net (code "248") (name "Net-(J4-Pad5)") (class "Default")
      (node (ref "J4") (pin "5") (pintype "input"))
      (node (ref "U1") (pin "320") (pintype "input"))
    )
    (net (code "249") (name "Net-(J4-Pad6)") (class "Default")
      (node (ref "J4") (pin "6") (pintype "input"))
      (node (ref "U1") (pin "319") (pintype "input"))
    )
    (net (code "250") (name "Net-(J4-Pad7)") (class "Default")
      (node (ref "J4") (pin "7") (pintype "input"))
      (node (ref "U1") (pin "318") (pintype "input"))
    )
    (net (code "251") (name "Net-(J4-Pad8)") (class "Default")
      (node (ref "J4") (pin "8") (pintype "input"))
      (node (ref "U1") (pin "317") (pintype "input"))
    )
    (net (code "252") (name "Net-(J4-Pad9)") (class "Default")
      (node (ref "J4") (pin "9") (pintype "input"))
      (node (ref "U1") (pin "316") (pintype "input"))
    )
    (net (code "253") (name "Net-(J4-Pad10)") (class "Default")
      (node (ref "J4") (pin "10") (pintype "input"))
      (node (ref "U1") (pin "315") (pintype "input"))
    )
    (net (code "254") (name "Net-(J4-Pad11)") (class "Default")
      (node (ref "J4") (pin "11") (pintype "input"))
      (node (ref "U1") (pin "314") (pintype "input"))
    )
    (net (code "255") (name "Net-(J4-Pad12)") (class "Default")
      (node (ref "J4") (pin "12") (pintype "input"))
      (node (ref "U1") (pin "313") (pintype "input"))
    )
    (net (code "256") (name "Net-(J4-Pad13)") (class "Default")
      (node (ref "J4") (pin "13") (pintype "input"))
      (node (ref "U1") (pin "312") (pintype "input"))
    )
    (net (code "257") (name "Net-(J4-Pad14)") (class "Default")
      (node (ref "J4") (pin "14") (pintype "input"))
      (node (ref "U1") (pin "311") (pintype "input"))
    )
    (net (code "258") (name "Net-(J4-Pad15)") (class "Default")
      (node (ref "J4") (pin "15") (pintype "input"))
      (node (ref "U1") (pin "310") (pintype "input"))
    )
    (net (code "259") (name "Net-(J4-Pad16)") (class "Default")
      (node (ref "J4") (pin "16") (pintype "input"))
      (node (ref "U1") (pin "309") (pintype "input"))
    )
    (net (code "260") (name "Net-(J4-Pad17)") (class "Default")
      (node (ref "J4") (pin "17") (pintype "input"))
      (node (ref "U1") (pin "308") (pintype "input"))
    )
    (net (code "261") (name "Net-(J4-Pad18)") (class "Default")
      (node (ref "J4") (pin "18") (pintype "input"))
      (node (ref "U1") (pin "307") (pintype "input"))
    )
    (net (code "262") (name "Net-(J4-Pad19)") (class "Default")
      (node (ref "J4") (pin "19") (pintype "input"))
      (node (ref "U1") (pin "306") (pintype "input"))
    )
    (net (code "263") (name "Net-(J4-Pad20)") (class "Default")
      (node (ref "J4") (pin "20") (pintype "input"))
      (node (ref "U1") (pin "305") (pintype "input"))
    )
    (net (code "264") (name "Net-(J4-Pad21)") (class "Default")
      (node (ref "J4") (pin "21") (pintype "input"))
      (node (ref "U1") (pin "304") (pintype "input"))
    )
    (net (code "265") (name "Net-(J4-Pad22)") (class "Default")
      (node (ref "J4") (pin "22") (pintype "input"))
      (node (ref "U1") (pin "303") (pintype "input"))
    )
    (net (code "266") (name "Net-(J4-Pad23)") (class "Default")
      (node (ref "J4") (pin "23") (pintype "input"))
      (node (ref "U1") (pin "302") (pintype "input"))
    )
    (net (code "267") (name "Net-(J4-Pad24)") (class "Default")
      (node (ref "J4") (pin "24") (pintype "input"))
      (node (ref "U1") (pin "301") (pintype "input"))
    )
    (net (code "268") (name "Net-(J4-Pad25)") (class "Default")
      (node (ref "J4") (pin "25") (pintype "input"))
      (node (ref "U1") (pin "300") (pintype "input"))
    )
    (net (code "269") (name "Net-(J4-Pad26)") (class "Default")
      (node (ref "J4") (pin "26") (pintype "input"))
      (node (ref "U1") (pin "299") (pintype "input"))
    )
    (net (code "270") (name "Net-(J4-Pad27)") (class "Default")
      (node (ref "J4") (pin "27") (pintype "input"))
      (node (ref "U1") (pin "298") (pintype "input"))
    )
    (net (code "271") (name "Net-(J4-Pad28)") (class "Default")
      (node (ref "J4") (pin "28") (pintype "input"))
      (node (ref "U1") (pin "297") (pintype "input"))
    )
    (net (code "272") (name "Net-(J4-Pad29)") (class "Default")
      (node (ref "J4") (pin "29") (pintype "input"))
      (node (ref "U1") (pin "296") (pintype "input"))
    )
    (net (code "273") (name "Net-(J4-Pad30)") (class "Default")
      (node (ref "J4") (pin "30") (pintype "input"))
      (node (ref "U1") (pin "295") (pintype "input"))
    )
    (net (code "274") (name "Net-(J4-Pad31)") (class "Default")
      (node (ref "J4") (pin "31") (pintype "input"))
      (node (ref "U1") (pin "294") (pintype "input"))
    )
    (net (code "275") (name "Net-(J4-Pad32)") (class "Default")
      (node (ref "J4") (pin "32") (pintype "input"))
      (node (ref "U1") (pin "293") (pintype "input"))
    )
    (net (code "276") (name "Net-(J4-Pad33)") (class "Default")
      (node (ref "J4") (pin "33") (pintype "input"))
      (node (ref "U1") (pin "292") (pintype "input"))
    )
    (net (code "277") (name "Net-(J4-Pad34)") (class "Default")
      (node (ref "J4") (pin "34") (pintype "input"))
      (node (ref "U1") (pin "291") (pintype "input"))
    )
    (net (code "278") (name "Net-(J4-Pad35)") (class "Default")
      (node (ref "J4") (pin "35") (pintype "input"))
      (node (ref "U1") (pin "290") (pintype "input"))
    )
    (net (code "279") (name "Net-(J4-Pad36)") (class "Default")
      (node (ref "J4") (pin "36") (pintype "input"))
      (node (ref "U1") (pin "289") (pintype "input"))
    )
    (net (code "280") (name "Net-(J4-Pad37)") (class "Default")
      (node (ref "J4") (pin "37") (pintype "input"))
      (node (ref "U1") (pin "288") (pintype "input"))
    )
    (net (code "281") (name "Net-(J4-Pad38)") (class "Default")
      (node (ref "J4") (pin "38") (pintype "input"))
      (node (ref "U1") (pin "287") (pintype "input"))
    )
    (net (code "282") (name "Net-(J4-Pad39)") (class "Default")
      (node (ref "J4") (pin "39") (pintype "input"))
      (node (ref "U1") (pin "286") (pintype "input"))
    )
    (net (code "283") (name "Net-(J4-Pad40)") (class "Default")
      (node (ref "J4") (pin "40") (pintype "input"))
      (node (ref "U1") (pin "285") (pintype "input"))
    )
    (net (code "284") (name "Net-(J4-Pad41)") (class "Default")
      (node (ref "J4") (pin "41") (pintype "input"))
      (node (ref "U1") (pin "284") (pintype "input"))
    )
    (net (code "285") (name "Net-(J4-Pad42)") (class "Default")
      (node (ref "J4") (pin "42") (pintype "input"))
      (node (ref "U1") (pin "283") (pintype "input"))
    )
    (net (code "286") (name "Net-(J4-Pad43)") (class "Default")
      (node (ref "J4") (pin "43") (pintype "input"))
      (node (ref "U1") (pin "282") (pintype "input"))
    )
    (net (code "287") (name "Net-(J4-Pad44)") (class "Default")
      (node (ref "J4") (pin "44") (pintype "input"))
      (node (ref "U1") (pin "281") (pintype "input"))
    )
    (net (code "288") (name "Net-(J4-Pad45)") (class "Default")
      (node (ref "J4") (pin "45") (pintype "input"))
      (node (ref "U1") (pin "280") (pintype "input"))
    )
    (net (code "289") (name "Net-(J4-Pad46)") (class "Default")
      (node (ref "J4") (pin "46") (pintype "input"))
      (node (ref "U1") (pin "279") (pintype "input"))
    )
    (net (code "290") (name "Net-(J4-Pad47)") (class "Default")
      (node (ref "J4") (pin "47") (pintype "input"))
      (node (ref "U1") (pin "278") (pintype "input"))
    )
    (net (code "291") (name "Net-(J4-Pad48)") (class "Default")
      (node (ref "J4") (pin "48") (pintype "input"))
      (node (ref "U1") (pin "277") (pintype "input"))
    )
    (net (code "292") (name "Net-(J4-Pad49)") (class "Default")
      (node (ref "J4") (pin "49") (pintype "input"))
      (node (ref "U1") (pin "276") (pintype "input"))
    )
    (net (code "293") (name "Net-(J4-Pad50)") (class "Default")
      (node (ref "J4") (pin "50") (pintype "input"))
      (node (ref "U1") (pin "275") (pintype "input"))
    )
    (net (code "294") (name "Net-(J4-Pad51)") (class "Default")
      (node (ref "J4") (pin "51") (pintype "input"))
      (node (ref "U1") (pin "274") (pintype "input"))
    )
    (net (code "295") (name "Net-(J4-Pad52)") (class "Default")
      (node (ref "J4") (pin "52") (pintype "input"))
      (node (ref "U1") (pin "273") (pintype "input"))
    )
    (net (code "296") (name "Net-(J4-Pad53)") (class "Default")
      (node (ref "J4") (pin "53") (pintype "input"))
      (node (ref "U1") (pin "272") (pintype "input"))
    )
    (net (code "297") (name "Net-(J4-Pad54)") (class "Default")
      (node (ref "J4") (pin "54") (pintype "input"))
      (node (ref "U1") (pin "271") (pintype "input"))
    )
    (net (code "298") (name "Net-(J4-Pad55)") (class "Default")
      (node (ref "J4") (pin "55") (pintype "input"))
      (node (ref "U1") (pin "270") (pintype "input"))
    )
    (net (code "299") (name "Net-(J4-Pad56)") (class "Default")
      (node (ref "J4") (pin "56") (pintype "input"))
      (node (ref "U1") (pin "269") (pintype "input"))
    )
    (net (code "300") (name "Net-(J4-Pad57)") (class "Default")
      (node (ref "J4") (pin "57") (pintype "input"))
      (node (ref "U1") (pin "268") (pintype "input"))
    )
    (net (code "301") (name "Net-(J4-Pad58)") (class "Default")
      (node (ref "J4") (pin "58") (pintype "input"))
      (node (ref "U1") (pin "267") (pintype "input"))
    )
    (net (code "302") (name "Net-(J4-Pad59)") (class "Default")
      (node (ref "J4") (pin "59") (pintype "input"))
      (node (ref "U1") (pin "266") (pintype "input"))
    )
    (net (code "303") (name "Net-(J4-Pad60)") (class "Default")
      (node (ref "J4") (pin "60") (pintype "input"))
      (node (ref "U1") (pin "265") (pintype "input"))
    )
    (net (code "304") (name "Net-(J4-Pad61)") (class "Default")
      (node (ref "J4") (pin "61") (pintype "input"))
      (node (ref "U1") (pin "264") (pintype "input"))
    )
    (net (code "305") (name "Net-(J4-Pad62)") (class "Default")
      (node (ref "J4") (pin "62") (pintype "input"))
      (node (ref "U1") (pin "263") (pintype "input"))
    )
    (net (code "306") (name "Net-(J4-Pad63)") (class "Default")
      (node (ref "J4") (pin "63") (pintype "input"))
      (node (ref "U1") (pin "262") (pintype "input"))
    )
    (net (code "307") (name "Net-(J4-Pad64)") (class "Default")
      (node (ref "J4") (pin "64") (pintype "input"))
      (node (ref "U1") (pin "261") (pintype "input"))
    )
    (net (code "308") (name "Net-(J4-Pad65)") (class "Default")
      (node (ref "J4") (pin "65") (pintype "input"))
      (node (ref "U1") (pin "260") (pintype "input"))
    )
    (net (code "309") (name "Net-(J4-Pad66)") (class "Default")
      (node (ref "J4") (pin "66") (pintype "input"))
      (node (ref "U1") (pin "259") (pintype "input"))
    )
    (net (code "310") (name "Net-(J4-Pad67)") (class "Default")
      (node (ref "J4") (pin "67") (pintype "input"))
      (node (ref "U1") (pin "258") (pintype "input"))
    )
    (net (code "311") (name "Net-(J4-Pad68)") (class "Default")
      (node (ref "J4") (pin "68") (pintype "input"))
      (node (ref "U1") (pin "257") (pintype "input"))
    )
    (net (code "312") (name "Net-(J4-Pad69)") (class "Default")
      (node (ref "J4") (pin "69") (pintype "input"))
      (node (ref "U1") (pin "256") (pintype "input"))
    )
    (net (code "313") (name "Net-(J4-Pad70)") (class "Default")
      (node (ref "J4") (pin "70") (pintype "input"))
      (node (ref "U1") (pin "255") (pintype "input"))
    )
    (net (code "314") (name "Net-(J4-Pad71)") (class "Default")
      (node (ref "J4") (pin "71") (pintype "input"))
      (node (ref "U1") (pin "254") (pintype "input"))
    )
    (net (code "315") (name "Net-(J4-Pad72)") (class "Default")
      (node (ref "J4") (pin "72") (pintype "input"))
      (node (ref "U1") (pin "253") (pintype "input"))
    )
    (net (code "316") (name "Net-(J4-Pad73)") (class "Default")
      (node (ref "J4") (pin "73") (pintype "input"))
      (node (ref "U1") (pin "252") (pintype "input"))
    )
    (net (code "317") (name "Net-(J4-Pad74)") (class "Default")
      (node (ref "J4") (pin "74") (pintype "input"))
      (node (ref "U1") (pin "251") (pintype "input"))
    )
    (net (code "318") (name "Net-(J4-Pad75)") (class "Default")
      (node (ref "J4") (pin "75") (pintype "input"))
      (node (ref "U1") (pin "250") (pintype "input"))
    )
    (net (code "319") (name "Net-(J4-Pad76)") (class "Default")
      (node (ref "J4") (pin "76") (pintype "input"))
      (node (ref "U1") (pin "249") (pintype "input"))
    )
    (net (code "320") (name "Net-(J4-Pad77)") (class "Default")
      (node (ref "J4") (pin "77") (pintype "input"))
      (node (ref "U1") (pin "248") (pintype "input"))
    )
    (net (code "321") (name "Net-(J4-Pad78)") (class "Default")
      (node (ref "J4") (pin "78") (pintype "input"))
      (node (ref "U1") (pin "247") (pintype "input"))
    )
    (net (code "322") (name "Net-(J4-Pad79)") (class "Default")
      (node (ref "J4") (pin "79") (pintype "input"))
      (node (ref "U1") (pin "246") (pintype "input"))
    )
    (net (code "323") (name "Net-(J4-Pad80)") (class "Default")
      (node (ref "J4") (pin "80") (pintype "input"))
      (node (ref "U1") (pin "245") (pintype "input"))
    )
    (net (code "324") (name "Net-(J4-Pad81)") (class "Default")
      (node (ref "J4") (pin "81") (pintype "input"))
      (node (ref "U1") (pin "244") (pintype "input"))
    )
  )
)
